# Sensors.net
KiCad netlist of a schematic drawn in EAGLE
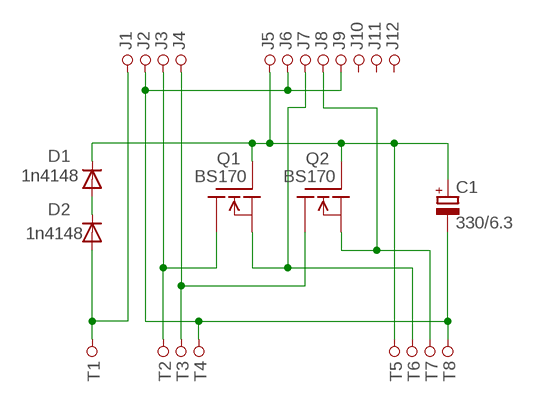
[diagram p0: schematic, sheet 1]

(export (version "E")
  (design (tool "Eeschema 10.0.6"))
  (components
    (comp (ref "C1")
      (value "330/6.3")
      (footprint "eagle-import:E2,5-6")
      (libsource (lib "eagle-import") (part "CPOL-EUE2.5-6"))
    )
    (comp (ref "D1")
      (value "1n4148")
      (footprint "eagle-import:DO34Z7")
      (libsource (lib "eagle-import") (part "1N4148"))
    )
    (comp (ref "D2")
      (value "1n4148")
      (footprint "eagle-import:DO34Z7")
      (libsource (lib "eagle-import") (part "1N4148"))
    )
    (comp (ref "J1")
      (value "PINHDR-1X1")
      (footprint "eagle-import:HDR1X1")
      (libsource (lib "eagle-import") (part "PINHDR-1X1"))
    )
    (comp (ref "J2")
      (value "PINHDR-1X1")
      (footprint "eagle-import:HDR1X1")
      (libsource (lib "eagle-import") (part "PINHDR-1X1"))
    )
    (comp (ref "J3")
      (value "PINHDR-1X1")
      (footprint "eagle-import:HDR1X1")
      (libsource (lib "eagle-import") (part "PINHDR-1X1"))
    )
    (comp (ref "J4")
      (value "PINHDR-1X1")
      (footprint "eagle-import:HDR1X1")
      (libsource (lib "eagle-import") (part "PINHDR-1X1"))
    )
    (comp (ref "J5")
      (value "PINHDR-1X1")
      (footprint "eagle-import:HDR1X1")
      (libsource (lib "eagle-import") (part "PINHDR-1X1"))
    )
    (comp (ref "J6")
      (value "PINHDR-1X1")
      (footprint "eagle-import:HDR1X1")
      (libsource (lib "eagle-import") (part "PINHDR-1X1"))
    )
    (comp (ref "J7")
      (value "PINHDR-1X1")
      (footprint "eagle-import:HDR1X1")
      (libsource (lib "eagle-import") (part "PINHDR-1X1"))
    )
    (comp (ref "J8")
      (value "PINHDR-1X1")
      (footprint "eagle-import:HDR1X1")
      (libsource (lib "eagle-import") (part "PINHDR-1X1"))
    )
    (comp (ref "J9")
      (value "PINHDR-1X1")
      (footprint "eagle-import:HDR1X1")
      (libsource (lib "eagle-import") (part "PINHDR-1X1"))
    )
    (comp (ref "J10")
      (value "PINHDR-1X1")
      (footprint "eagle-import:HDR1X1")
      (libsource (lib "eagle-import") (part "PINHDR-1X1"))
    )
    (comp (ref "J11")
      (value "PINHDR-1X1")
      (footprint "eagle-import:HDR1X1")
      (libsource (lib "eagle-import") (part "PINHDR-1X1"))
    )
    (comp (ref "J12")
      (value "PINHDR-1X1")
      (footprint "eagle-import:HDR1X1")
      (libsource (lib "eagle-import") (part "PINHDR-1X1"))
    )
    (comp (ref "Q1")
      (value "BS170")
      (footprint "eagle-import:TO92")
      (libsource (lib "eagle-import") (part "NFET"))
    )
    (comp (ref "Q2")
      (value "BS170")
      (footprint "eagle-import:TO92")
      (libsource (lib "eagle-import") (part "NFET"))
    )
    (comp (ref "T1")
      (value "PINHDR-1X1")
      (footprint "eagle-import:HDR1X1")
      (libsource (lib "eagle-import") (part "PINHDR-1X1"))
    )
    (comp (ref "T2")
      (value "PINHDR-1X1")
      (footprint "eagle-import:HDR1X1")
      (libsource (lib "eagle-import") (part "PINHDR-1X1"))
    )
    (comp (ref "T3")
      (value "PINHDR-1X1")
      (footprint "eagle-import:HDR1X1")
      (libsource (lib "eagle-import") (part "PINHDR-1X1"))
    )
    (comp (ref "T4")
      (value "PINHDR-1X1")
      (footprint "eagle-import:HDR1X1")
      (libsource (lib "eagle-import") (part "PINHDR-1X1"))
    )
    (comp (ref "T5")
      (value "PINHDR-1X1")
      (footprint "eagle-import:HDR1X1")
      (libsource (lib "eagle-import") (part "PINHDR-1X1"))
    )
    (comp (ref "T6")
      (value "PINHDR-1X1")
      (footprint "eagle-import:HDR1X1")
      (libsource (lib "eagle-import") (part "PINHDR-1X1"))
    )
    (comp (ref "T7")
      (value "PINHDR-1X1")
      (footprint "eagle-import:HDR1X1")
      (libsource (lib "eagle-import") (part "PINHDR-1X1"))
    )
    (comp (ref "T8")
      (value "PINHDR-1X1")
      (footprint "eagle-import:HDR1X1")
      (libsource (lib "eagle-import") (part "PINHDR-1X1"))
    )
  )
  (nets
    (net (code "1") (name "Net-(D1-PadA)") (class "Default")
      (node (ref "D1") (pin "A") (pinfunction "A_A") (pintype "passive"))
      (node (ref "D2") (pin "C") (pinfunction "C_C") (pintype "passive"))
    )
    (net (code "2") (name "Net-(J1-.)") (class "Default")
      (node (ref "D2") (pin "A") (pinfunction "A_A") (pintype "passive"))
      (node (ref "J1") (pin "1") (pinfunction "._1") (pintype "passive"))
      (node (ref "T1") (pin "1") (pinfunction "._1") (pintype "passive"))
    )
    (net (code "3") (name "Net-(J2-.)") (class "Default")
      (node (ref "C1") (pin "-") (pinfunction "-_-") (pintype "passive"))
      (node (ref "J2") (pin "1") (pinfunction "._1") (pintype "passive"))
      (node (ref "J6") (pin "1") (pinfunction "._1") (pintype "passive"))
      (node (ref "J9") (pin "1") (pinfunction "._1") (pintype "passive"))
      (node (ref "T4") (pin "1") (pinfunction "._1") (pintype "passive"))
      (node (ref "T8") (pin "1") (pinfunction "._1") (pintype "passive"))
    )
    (net (code "4") (name "Net-(J3-.)") (class "Default")
      (node (ref "J3") (pin "1") (pinfunction "._1") (pintype "passive"))
      (node (ref "Q1") (pin "3") (pinfunction "D_3") (pintype "passive"))
      (node (ref "T2") (pin "1") (pinfunction "._1") (pintype "passive"))
    )
    (net (code "5") (name "Net-(J4-.)") (class "Default")
      (node (ref "J4") (pin "1") (pinfunction "._1") (pintype "passive"))
      (node (ref "Q2") (pin "3") (pinfunction "D_3") (pintype "passive"))
      (node (ref "T3") (pin "1") (pinfunction "._1") (pintype "passive"))
    )
    (net (code "6") (name "Net-(J5-.)") (class "Default")
      (node (ref "C1") (pin "+") (pinfunction "+_+") (pintype "passive"))
      (node (ref "D1") (pin "C") (pinfunction "C_C") (pintype "passive"))
      (node (ref "J5") (pin "1") (pinfunction "._1") (pintype "passive"))
      (node (ref "Q1") (pin "2") (pinfunction "G_2") (pintype "passive"))
      (node (ref "Q2") (pin "2") (pinfunction "G_2") (pintype "passive"))
      (node (ref "T5") (pin "1") (pinfunction "._1") (pintype "passive"))
    )
    (net (code "7") (name "Net-(J7-.)") (class "Default")
      (node (ref "J7") (pin "1") (pinfunction "._1") (pintype "passive"))
      (node (ref "Q1") (pin "1") (pinfunction "S_1") (pintype "passive"))
      (node (ref "T6") (pin "1") (pinfunction "._1") (pintype "passive"))
    )
    (net (code "8") (name "Net-(J8-.)") (class "Default")
      (node (ref "J8") (pin "1") (pinfunction "._1") (pintype "passive"))
      (node (ref "Q2") (pin "1") (pinfunction "S_1") (pintype "passive"))
      (node (ref "T7") (pin "1") (pinfunction "._1") (pintype "passive"))
    )
    (net (code "9") (name "unconnected-(J10-.-Pad1)") (class "Default")
      (node (ref "J10") (pin "1") (pinfunction "._1") (pintype "passive"))
    )
    (net (code "10") (name "unconnected-(J11-.-Pad1)") (class "Default")
      (node (ref "J11") (pin "1") (pinfunction "._1") (pintype "passive"))
    )
    (net (code "11") (name "unconnected-(J12-.-Pad1)") (class "Default")
      (node (ref "J12") (pin "1") (pinfunction "._1") (pintype "passive"))
    )
  )
)
